# PCB-ENCODER4.net
KiCad netlist of a schematic drawn in EAGLE
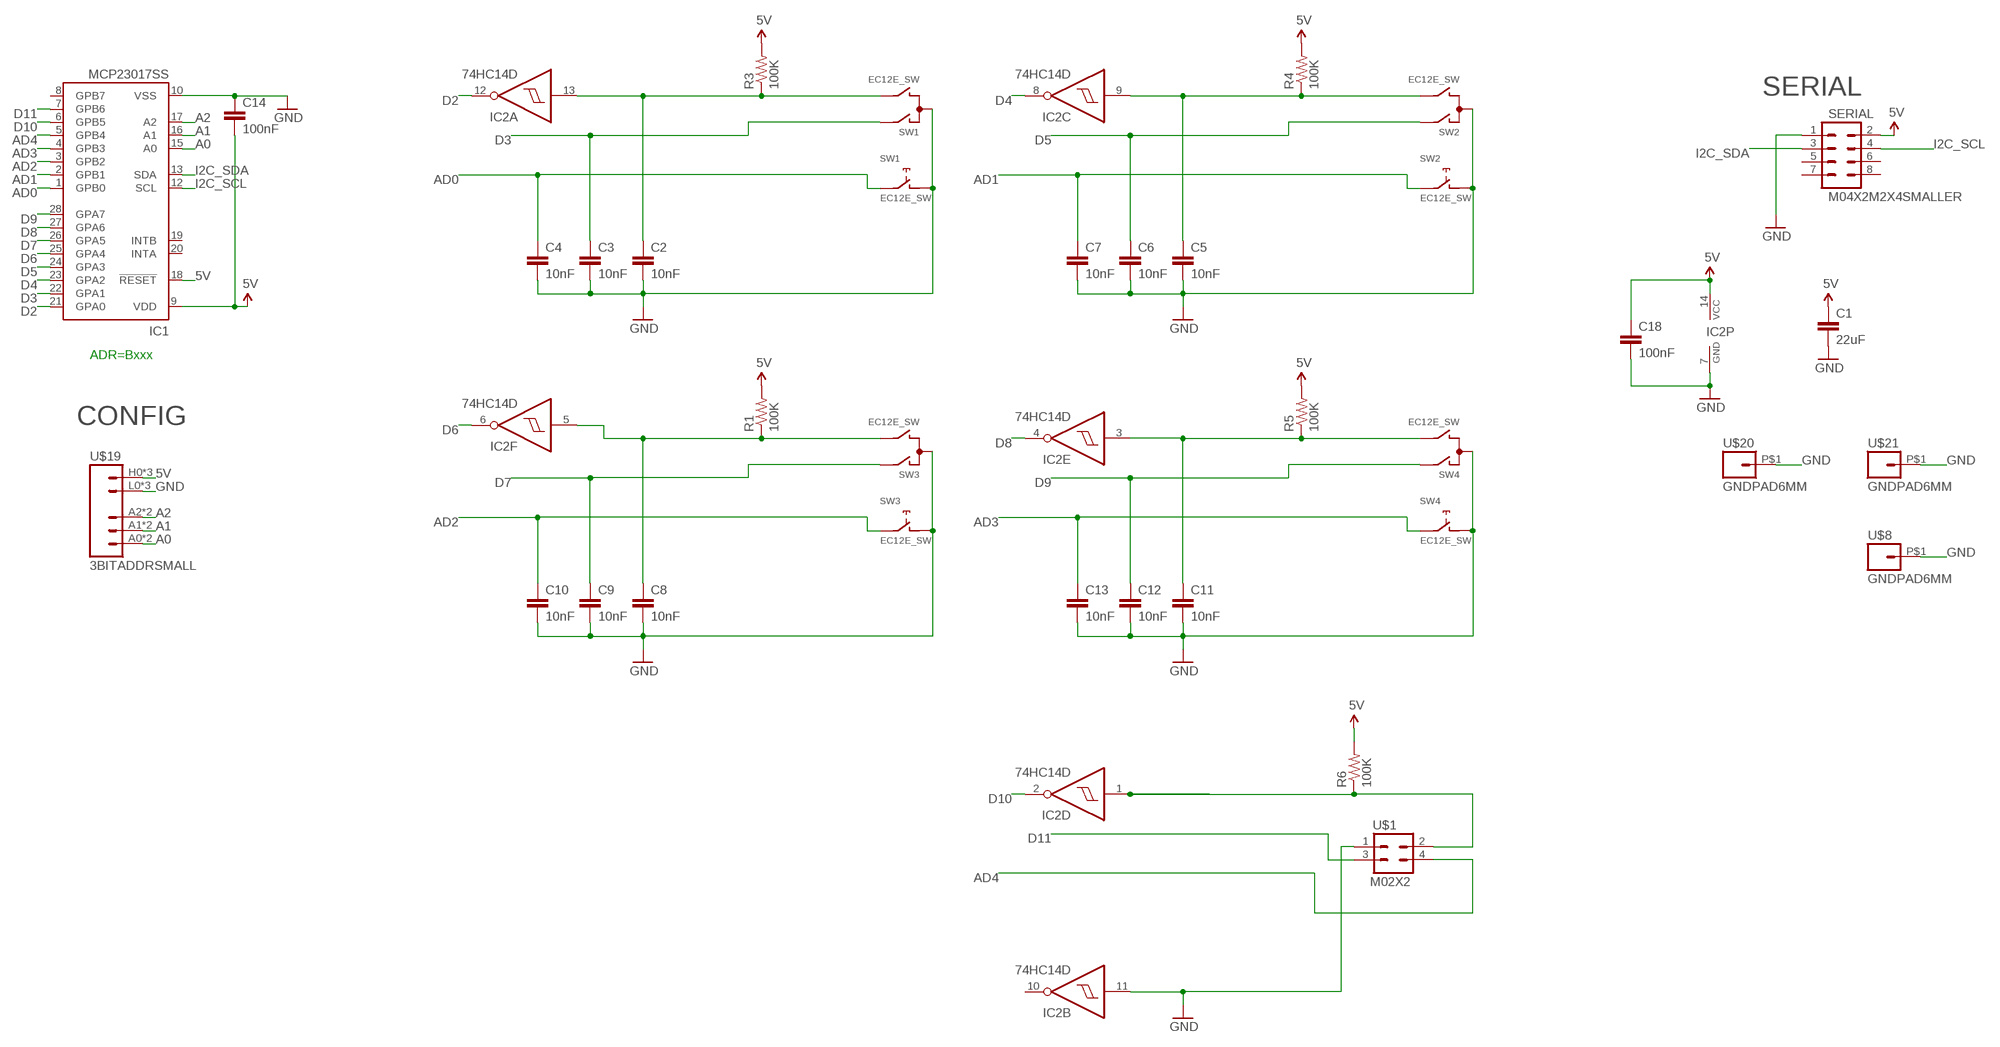
[diagram p0: schematic, sheet 1]

(export (version "E")
  (design (tool "Eeschema 10.0.6"))
  (components
    (comp (ref "C1")
      (value "22uF")
      (footprint "eagle-import:0805")
      (libsource (lib "eagle-import") (part "CAP0805"))
    )
    (comp (ref "C2")
      (value "10nF")
      (footprint "eagle-import:0603-CAP")
      (libsource (lib "eagle-import") (part "CAP0603-CAP"))
    )
    (comp (ref "C3")
      (value "10nF")
      (footprint "eagle-import:0603-CAP")
      (libsource (lib "eagle-import") (part "CAP0603-CAP"))
    )
    (comp (ref "C4")
      (value "10nF")
      (footprint "eagle-import:0603-CAP")
      (libsource (lib "eagle-import") (part "CAP0603-CAP"))
    )
    (comp (ref "C5")
      (value "10nF")
      (footprint "eagle-import:0603-CAP")
      (libsource (lib "eagle-import") (part "CAP0603-CAP"))
    )
    (comp (ref "C6")
      (value "10nF")
      (footprint "eagle-import:0603-CAP")
      (libsource (lib "eagle-import") (part "CAP0603-CAP"))
    )
    (comp (ref "C7")
      (value "10nF")
      (footprint "eagle-import:0603-CAP")
      (libsource (lib "eagle-import") (part "CAP0603-CAP"))
    )
    (comp (ref "C8")
      (value "10nF")
      (footprint "eagle-import:0603-CAP")
      (libsource (lib "eagle-import") (part "CAP0603-CAP"))
    )
    (comp (ref "C9")
      (value "10nF")
      (footprint "eagle-import:0603-CAP")
      (libsource (lib "eagle-import") (part "CAP0603-CAP"))
    )
    (comp (ref "C10")
      (value "10nF")
      (footprint "eagle-import:0603-CAP")
      (libsource (lib "eagle-import") (part "CAP0603-CAP"))
    )
    (comp (ref "C11")
      (value "10nF")
      (footprint "eagle-import:0603-CAP")
      (libsource (lib "eagle-import") (part "CAP0603-CAP"))
    )
    (comp (ref "C12")
      (value "10nF")
      (footprint "eagle-import:0603-CAP")
      (libsource (lib "eagle-import") (part "CAP0603-CAP"))
    )
    (comp (ref "C13")
      (value "10nF")
      (footprint "eagle-import:0603-CAP")
      (libsource (lib "eagle-import") (part "CAP0603-CAP"))
    )
    (comp (ref "C14")
      (value "100nF")
      (footprint "eagle-import:0603-CAP")
      (libsource (lib "eagle-import") (part "CAP0603-CAP"))
    )
    (comp (ref "C18")
      (value "100nF")
      (footprint "eagle-import:0603-CAP")
      (libsource (lib "eagle-import") (part "CAP0603-CAP"))
    )
    (comp (ref "IC1")
      (value "MCP23017SS")
      (footprint "eagle-import:SSOP28")
      (fields
        (field (name "MF") "MICROCHIP")
        (field (name "MPN") "MCP23017-E/SS")
        (field (name "MPN_1") "MCP23017-E/SS")
        (field (name "OC_FARNELL") "1467674")
        (field (name "OC_NEWARK") "31K2960")
      )
      (libsource (lib "eagle-import") (part "MCP23017SS"))
    )
    (comp (ref "IC2")
      (value "74HC14D")
      (footprint "eagle-import:SO14")
      (libsource (lib "eagle-import") (part "7414DHC"))
    )
    (comp (ref "R1")
      (value "100K")
      (footprint "eagle-import:0603-RES")
      (libsource (lib "eagle-import") (part "RESISTOR0603-RES"))
    )
    (comp (ref "R3")
      (value "100K")
      (footprint "eagle-import:0603-RES")
      (libsource (lib "eagle-import") (part "RESISTOR0603-RES"))
    )
    (comp (ref "R4")
      (value "100K")
      (footprint "eagle-import:0603-RES")
      (libsource (lib "eagle-import") (part "RESISTOR0603-RES"))
    )
    (comp (ref "R5")
      (value "100K")
      (footprint "eagle-import:0603-RES")
      (libsource (lib "eagle-import") (part "RESISTOR0603-RES"))
    )
    (comp (ref "R6")
      (value "100K")
      (footprint "eagle-import:0603-RES")
      (libsource (lib "eagle-import") (part "RESISTOR0603-RES"))
    )
    (comp (ref "SERIAL")
      (value "M04X2M2X4SMALLER")
      (footprint "eagle-import:M2X4SMALLER")
      (libsource (lib "eagle-import") (part "M04X2M2X4SMALLER"))
    )
    (comp (ref "SW1")
      (value "EC12E_SW")
      (footprint "eagle-import:ALPS_EC12E_SW")
      (fields (field (name "MPN") "EC12E2424407"))
      (libsource (lib "eagle-import") (part "EC12E_SW"))
    )
    (comp (ref "SW2")
      (value "EC12E_SW")
      (footprint "eagle-import:ALPS_EC12E_SW")
      (fields (field (name "MPN") "EC12E2424407"))
      (libsource (lib "eagle-import") (part "EC12E_SW"))
    )
    (comp (ref "SW3")
      (value "EC12E_SW")
      (footprint "eagle-import:ALPS_EC12E_SW")
      (fields (field (name "MPN") "EC12E2424407"))
      (libsource (lib "eagle-import") (part "EC12E_SW"))
    )
    (comp (ref "SW4")
      (value "EC12E_SW")
      (footprint "eagle-import:ALPS_EC12E_SW")
      (fields (field (name "MPN") "EC12E2424407"))
      (libsource (lib "eagle-import") (part "EC12E_SW"))
    )
    (comp (ref "U$1")
      (value "M02X2")
      (footprint "eagle-import:2X2")
      (libsource (lib "eagle-import") (part "M02X2"))
    )
    (comp (ref "U$8")
      (value "GNDPAD6MM")
      (footprint "eagle-import:3.2MMPAD6MM")
      (libsource (lib "eagle-import") (part "GNDPAD6MM"))
    )
    (comp (ref "U$19")
      (value "3BITADDRSMALL")
      (footprint "eagle-import:3BITADDR_SMALL")
      (libsource (lib "eagle-import") (part "3BITADDRSMALL"))
    )
    (comp (ref "U$20")
      (value "GNDPAD6MM")
      (footprint "eagle-import:3.2MMPAD6MM")
      (libsource (lib "eagle-import") (part "GNDPAD6MM"))
    )
    (comp (ref "U$21")
      (value "GNDPAD6MM")
      (footprint "eagle-import:3.2MMPAD6MM")
      (libsource (lib "eagle-import") (part "GNDPAD6MM"))
    )
  )
  (nets
    (net (code "1") (name "/A0") (class "Default")
      (node (ref "IC1") (pin "15") (pinfunction "A0_15") (pintype "input"))
      (node (ref "U$19") (pin "A0") (pinfunction "A0_A0") (pintype "passive"))
      (node (ref "U$19") (pin "AS0") (pinfunction "A0_AS0") (pintype "passive"))
    )
    (net (code "2") (name "/A1") (class "Default")
      (node (ref "IC1") (pin "16") (pinfunction "A1_16") (pintype "input"))
      (node (ref "U$19") (pin "A1") (pinfunction "A1_A1") (pintype "passive"))
      (node (ref "U$19") (pin "AS1") (pinfunction "A1_AS1") (pintype "passive"))
    )
    (net (code "3") (name "/A2") (class "Default")
      (node (ref "IC1") (pin "17") (pinfunction "A2_17") (pintype "input"))
      (node (ref "U$19") (pin "A2") (pinfunction "A2_A2") (pintype "passive"))
      (node (ref "U$19") (pin "AS2") (pinfunction "A2_AS2") (pintype "passive"))
    )
    (net (code "4") (name "/AD0") (class "Default")
      (node (ref "C4") (pin "1") (pinfunction "1_1") (pintype "passive"))
      (node (ref "IC1") (pin "1") (pinfunction "GPB0_1") (pintype "bidirectional"))
      (node (ref "SW1") (pin "E") (pinfunction "2_E") (pintype "passive"))
    )
    (net (code "5") (name "/AD1") (class "Default")
      (node (ref "C7") (pin "1") (pinfunction "1_1") (pintype "passive"))
      (node (ref "IC1") (pin "2") (pinfunction "GPB1_2") (pintype "bidirectional"))
      (node (ref "SW2") (pin "E") (pinfunction "2_E") (pintype "passive"))
    )
    (net (code "6") (name "/AD2") (class "Default")
      (node (ref "C10") (pin "1") (pinfunction "1_1") (pintype "passive"))
      (node (ref "IC1") (pin "3") (pinfunction "GPB2_3") (pintype "bidirectional"))
      (node (ref "SW3") (pin "E") (pinfunction "2_E") (pintype "passive"))
    )
    (net (code "7") (name "/AD3") (class "Default")
      (node (ref "C13") (pin "1") (pinfunction "1_1") (pintype "passive"))
      (node (ref "IC1") (pin "4") (pinfunction "GPB3_4") (pintype "bidirectional"))
      (node (ref "SW4") (pin "E") (pinfunction "2_E") (pintype "passive"))
    )
    (net (code "8") (name "/AD4") (class "Default")
      (node (ref "IC1") (pin "5") (pinfunction "GPB4_5") (pintype "bidirectional"))
      (node (ref "U$1") (pin "4") (pinfunction "4_4") (pintype "passive"))
    )
    (net (code "9") (name "/D2") (class "Default")
      (node (ref "IC1") (pin "21") (pinfunction "GPA0_21") (pintype "bidirectional"))
      (node (ref "IC2") (pin "12") (pinfunction "O_12") (pintype "output"))
    )
    (net (code "10") (name "/D3") (class "Default")
      (node (ref "C3") (pin "1") (pinfunction "1_1") (pintype "passive"))
      (node (ref "IC1") (pin "22") (pinfunction "GPA1_22") (pintype "bidirectional"))
      (node (ref "SW1") (pin "A") (pinfunction "A_A") (pintype "passive"))
    )
    (net (code "11") (name "/D4") (class "Default")
      (node (ref "IC1") (pin "23") (pinfunction "GPA2_23") (pintype "bidirectional"))
      (node (ref "IC2") (pin "8") (pinfunction "O_8") (pintype "output"))
    )
    (net (code "12") (name "/D5") (class "Default")
      (node (ref "C6") (pin "1") (pinfunction "1_1") (pintype "passive"))
      (node (ref "IC1") (pin "24") (pinfunction "GPA3_24") (pintype "bidirectional"))
      (node (ref "SW2") (pin "A") (pinfunction "A_A") (pintype "passive"))
    )
    (net (code "13") (name "/D6") (class "Default")
      (node (ref "IC1") (pin "25") (pinfunction "GPA4_25") (pintype "bidirectional"))
      (node (ref "IC2") (pin "6") (pinfunction "O_6") (pintype "output"))
    )
    (net (code "14") (name "/D7") (class "Default")
      (node (ref "C9") (pin "1") (pinfunction "1_1") (pintype "passive"))
      (node (ref "IC1") (pin "26") (pinfunction "GPA5_26") (pintype "bidirectional"))
      (node (ref "SW3") (pin "A") (pinfunction "A_A") (pintype "passive"))
    )
    (net (code "15") (name "/D8") (class "Default")
      (node (ref "IC1") (pin "27") (pinfunction "GPA6_27") (pintype "bidirectional"))
      (node (ref "IC2") (pin "4") (pinfunction "O_4") (pintype "output"))
    )
    (net (code "16") (name "/D9") (class "Default")
      (node (ref "C12") (pin "1") (pinfunction "1_1") (pintype "passive"))
      (node (ref "IC1") (pin "28") (pinfunction "GPA7_28") (pintype "bidirectional"))
      (node (ref "SW4") (pin "A") (pinfunction "A_A") (pintype "passive"))
    )
    (net (code "17") (name "/D10") (class "Default")
      (node (ref "IC1") (pin "6") (pinfunction "GPB5_6") (pintype "bidirectional"))
      (node (ref "IC2") (pin "2") (pinfunction "O_2") (pintype "output"))
    )
    (net (code "18") (name "/D11") (class "Default")
      (node (ref "IC1") (pin "7") (pinfunction "GPB6_7") (pintype "bidirectional"))
      (node (ref "U$1") (pin "3") (pinfunction "3_3") (pintype "passive"))
    )
    (net (code "19") (name "/I2C_SCL") (class "Default")
      (node (ref "IC1") (pin "12") (pinfunction "SCL_12") (pintype "input"))
      (node (ref "SERIAL") (pin "4") (pinfunction "4_4") (pintype "passive"))
    )
    (net (code "20") (name "/I2C_SDA") (class "Default")
      (node (ref "IC1") (pin "13") (pinfunction "SDA_13") (pintype "bidirectional"))
      (node (ref "SERIAL") (pin "3") (pinfunction "3_3") (pintype "passive"))
    )
    (net (code "21") (name "5V") (class "Default")
      (node (ref "C1") (pin "1") (pinfunction "1_1") (pintype "passive"))
      (node (ref "C14") (pin "2") (pinfunction "2_2") (pintype "passive"))
      (node (ref "C18") (pin "1") (pinfunction "1_1") (pintype "passive"))
      (node (ref "IC1") (pin "18") (pinfunction "~{RESET}_18") (pintype "input"))
      (node (ref "IC1") (pin "9") (pinfunction "VDD_9") (pintype "power_in"))
      (node (ref "IC2") (pin "14") (pinfunction "VCC_14") (pintype "power_in"))
      (node (ref "R1") (pin "2") (pinfunction "2_2") (pintype "passive"))
      (node (ref "R3") (pin "2") (pinfunction "2_2") (pintype "passive"))
      (node (ref "R4") (pin "2") (pinfunction "2_2") (pintype "passive"))
      (node (ref "R5") (pin "2") (pinfunction "2_2") (pintype "passive"))
      (node (ref "R6") (pin "2") (pinfunction "2_2") (pintype "passive"))
      (node (ref "SERIAL") (pin "2") (pinfunction "2_2") (pintype "passive"))
      (node (ref "U$19") (pin "H0") (pinfunction "VCC_H0") (pintype "passive"))
      (node (ref "U$19") (pin "H1") (pinfunction "VCC_H1") (pintype "passive"))
      (node (ref "U$19") (pin "H2") (pinfunction "VCC_H2") (pintype "passive"))
    )
    (net (code "22") (name "GND") (class "Default")
      (node (ref "C1") (pin "2") (pinfunction "2_2") (pintype "passive"))
      (node (ref "C10") (pin "2") (pinfunction "2_2") (pintype "passive"))
      (node (ref "C11") (pin "2") (pinfunction "2_2") (pintype "passive"))
      (node (ref "C12") (pin "2") (pinfunction "2_2") (pintype "passive"))
      (node (ref "C13") (pin "2") (pinfunction "2_2") (pintype "passive"))
      (node (ref "C14") (pin "1") (pinfunction "1_1") (pintype "passive"))
      (node (ref "C18") (pin "2") (pinfunction "2_2") (pintype "passive"))
      (node (ref "C2") (pin "2") (pinfunction "2_2") (pintype "passive"))
      (node (ref "C3") (pin "2") (pinfunction "2_2") (pintype "passive"))
      (node (ref "C4") (pin "2") (pinfunction "2_2") (pintype "passive"))
      (node (ref "C5") (pin "2") (pinfunction "2_2") (pintype "passive"))
      (node (ref "C6") (pin "2") (pinfunction "2_2") (pintype "passive"))
      (node (ref "C7") (pin "2") (pinfunction "2_2") (pintype "passive"))
      (node (ref "C8") (pin "2") (pinfunction "2_2") (pintype "passive"))
      (node (ref "C9") (pin "2") (pinfunction "2_2") (pintype "passive"))
      (node (ref "IC1") (pin "10") (pinfunction "VSS_10") (pintype "power_in"))
      (node (ref "IC2") (pin "11") (pinfunction "I_11") (pintype "input"))
      (node (ref "IC2") (pin "7") (pinfunction "GND_7") (pintype "power_in"))
      (node (ref "SERIAL") (pin "1") (pinfunction "1_1") (pintype "passive"))
      (node (ref "SW1") (pin "C") (pinfunction "C_C") (pintype "passive"))
      (node (ref "SW1") (pin "D") (pinfunction "1_D") (pintype "passive"))
      (node (ref "SW2") (pin "C") (pinfunction "C_C") (pintype "passive"))
      (node (ref "SW2") (pin "D") (pinfunction "1_D") (pintype "passive"))
      (node (ref "SW3") (pin "C") (pinfunction "C_C") (pintype "passive"))
      (node (ref "SW3") (pin "D") (pinfunction "1_D") (pintype "passive"))
      (node (ref "SW4") (pin "C") (pinfunction "C_C") (pintype "passive"))
      (node (ref "SW4") (pin "D") (pinfunction "1_D") (pintype "passive"))
      (node (ref "U$1") (pin "1") (pinfunction "1_1") (pintype "passive"))
      (node (ref "U$19") (pin "L0") (pinfunction "GND_L0") (pintype "passive"))
      (node (ref "U$19") (pin "L1") (pinfunction "GND_L1") (pintype "passive"))
      (node (ref "U$19") (pin "L2") (pinfunction "GND_L2") (pintype "passive"))
      (node (ref "U$20") (pin "P$1") (pinfunction "1_P$1") (pintype "passive"))
      (node (ref "U$21") (pin "P$1") (pinfunction "1_P$1") (pintype "passive"))
      (node (ref "U$8") (pin "P$1") (pinfunction "1_P$1") (pintype "passive"))
    )
    (net (code "23") (name "Net-(IC2A-I)") (class "Default")
      (node (ref "C2") (pin "1") (pinfunction "1_1") (pintype "passive"))
      (node (ref "IC2") (pin "13") (pinfunction "I_13") (pintype "input"))
      (node (ref "R3") (pin "1") (pinfunction "1_1") (pintype "passive"))
      (node (ref "SW1") (pin "B") (pinfunction "B_B") (pintype "passive"))
    )
    (net (code "24") (name "Net-(IC2C-I)") (class "Default")
      (node (ref "C5") (pin "1") (pinfunction "1_1") (pintype "passive"))
      (node (ref "IC2") (pin "9") (pinfunction "I_9") (pintype "input"))
      (node (ref "R4") (pin "1") (pinfunction "1_1") (pintype "passive"))
      (node (ref "SW2") (pin "B") (pinfunction "B_B") (pintype "passive"))
    )
    (net (code "25") (name "Net-(IC2D-I)") (class "Default")
      (node (ref "IC2") (pin "1") (pinfunction "I_1") (pintype "input"))
      (node (ref "R6") (pin "1") (pinfunction "1_1") (pintype "passive"))
      (node (ref "U$1") (pin "2") (pinfunction "2_2") (pintype "passive"))
    )
    (net (code "26") (name "Net-(IC2E-I)") (class "Default")
      (node (ref "C11") (pin "1") (pinfunction "1_1") (pintype "passive"))
      (node (ref "IC2") (pin "3") (pinfunction "I_3") (pintype "input"))
      (node (ref "R5") (pin "1") (pinfunction "1_1") (pintype "passive"))
      (node (ref "SW4") (pin "B") (pinfunction "B_B") (pintype "passive"))
    )
    (net (code "27") (name "Net-(IC2F-I)") (class "Default")
      (node (ref "C8") (pin "1") (pinfunction "1_1") (pintype "passive"))
      (node (ref "IC2") (pin "5") (pinfunction "I_5") (pintype "input"))
      (node (ref "R1") (pin "1") (pinfunction "1_1") (pintype "passive"))
      (node (ref "SW3") (pin "B") (pinfunction "B_B") (pintype "passive"))
    )
    (net (code "28") (name "unconnected-(IC1-GPB7-Pad8)") (class "Default")
      (node (ref "IC1") (pin "8") (pinfunction "GPB7_8") (pintype "bidirectional"))
    )
    (net (code "29") (name "unconnected-(IC1-INTA-Pad20)") (class "Default")
      (node (ref "IC1") (pin "20") (pinfunction "INTA_20") (pintype "output"))
    )
    (net (code "30") (name "unconnected-(IC1-INTB-Pad19)") (class "Default")
      (node (ref "IC1") (pin "19") (pinfunction "INTB_19") (pintype "output"))
    )
    (net (code "31") (name "unconnected-(IC2B-O-Pad10)") (class "Default")
      (node (ref "IC2") (pin "10") (pinfunction "O_10") (pintype "output"))
    )
    (net (code "32") (name "unconnected-(SERIAL-Pad5)") (class "Default")
      (node (ref "SERIAL") (pin "5") (pinfunction "5_5") (pintype "passive"))
    )
    (net (code "33") (name "unconnected-(SERIAL-Pad6)") (class "Default")
      (node (ref "SERIAL") (pin "6") (pinfunction "6_6") (pintype "passive"))
    )
    (net (code "34") (name "unconnected-(SERIAL-Pad7)") (class "Default")
      (node (ref "SERIAL") (pin "7") (pinfunction "7_7") (pintype "passive"))
    )
    (net (code "35") (name "unconnected-(SERIAL-Pad8)") (class "Default")
      (node (ref "SERIAL") (pin "8") (pinfunction "8_8") (pintype "passive"))
    )
  )
)
